# light.net
KiCad netlist of a schematic drawn in EAGLE
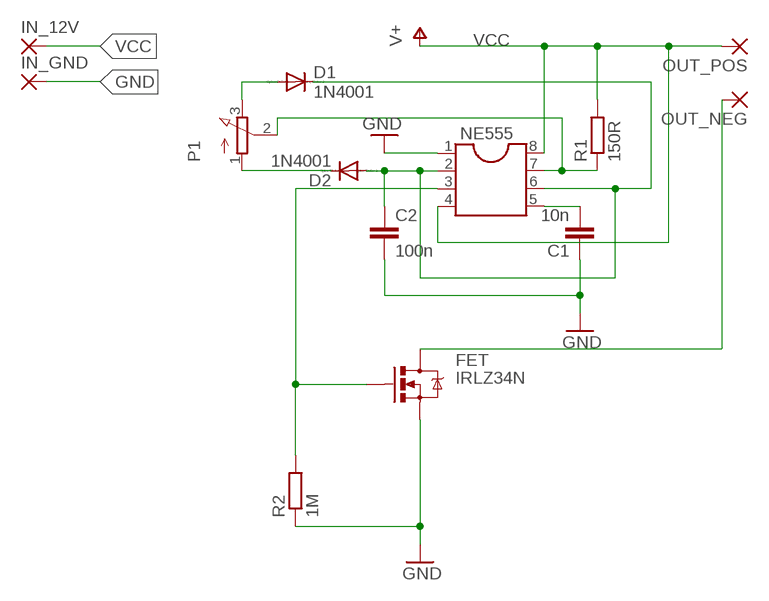
[diagram p0: schematic, sheet 1]

(export (version "E")
  (design (tool "Eeschema 10.0.6"))
  (components
    (comp (ref "C1")
      (value "10n")
      (footprint "eagle-import:C025-024X044")
      (libsource (lib "eagle-import") (part "C-EU025-024X044"))
    )
    (comp (ref "C2")
      (value "100n")
      (footprint "eagle-import:C025-024X044")
      (libsource (lib "eagle-import") (part "C-EU025-024X044"))
    )
    (comp (ref "D1")
      (value "1N4001")
      (footprint "eagle-import:DO41-10")
      (libsource (lib "eagle-import") (part "DIODE-DO41-10"))
    )
    (comp (ref "D2")
      (value "1N4001")
      (footprint "eagle-import:DO41-10")
      (libsource (lib "eagle-import") (part "DIODE-DO41-10"))
    )
    (comp (ref "FET")
      (value "IRLZ34N")
      (footprint "eagle-import:TO-220(2)")
      (fields (field (name "MF") "Infineon Technologies"))
      (libsource (lib "eagle-import") (part "IRLZ34N"))
    )
    (comp (ref "IN_12V")
      (value "3,81/1,3")
      (footprint "eagle-import:3,81_1,3")
      (libsource (lib "eagle-import") (part "3,81/1,3"))
    )
    (comp (ref "IN_GND")
      (value "3,81/1,3")
      (footprint "eagle-import:3,81_1,3")
      (libsource (lib "eagle-import") (part "3,81/1,3"))
    )
    (comp (ref "NE555")
      (value "DIL8")
      (footprint "eagle-import:DIL08")
      (libsource (lib "eagle-import") (part "DIL8"))
    )
    (comp (ref "OUT_NEG")
      (value "3,81/1,1")
      (footprint "eagle-import:3,81_1,1")
      (libsource (lib "eagle-import") (part "3,81/1,1"))
    )
    (comp (ref "OUT_POS")
      (value "3,81/1,1")
      (footprint "eagle-import:3,81_1,1")
      (libsource (lib "eagle-import") (part "3,81/1,1"))
    )
    (comp (ref "P1")
      (value "3RP/1610N")
      (footprint "eagle-import:3RP_1610N")
      (libsource (lib "eagle-import") (part "3RP/1610N"))
    )
    (comp (ref "R1")
      (value "150R")
      (footprint "eagle-import:0207_7")
      (libsource (lib "eagle-import") (part "R-EU_0207/7"))
    )
    (comp (ref "R2")
      (value "1M")
      (footprint "eagle-import:0207_7")
      (libsource (lib "eagle-import") (part "R-EU_0207/7"))
    )
  )
  (nets
    (net (code "1") (name "GND") (class "Default")
      (node (ref "C1") (pin "1") (pinfunction "1_1") (pintype "passive"))
      (node (ref "C2") (pin "2") (pinfunction "2_2") (pintype "passive"))
      (node (ref "FET") (pin "OUT") (pinfunction "S_OUT") (pintype "passive"))
      (node (ref "IN_GND") (pin "1") (pinfunction "P_1") (pintype "passive"))
      (node (ref "NE555") (pin "1") (pinfunction "1_1") (pintype "passive"))
      (node (ref "R2") (pin "1") (pinfunction "1_1") (pintype "passive"))
    )
    (net (code "2") (name "Net-(C1-Pad2)") (class "Default")
      (node (ref "C1") (pin "2") (pinfunction "2_2") (pintype "passive"))
      (node (ref "NE555") (pin "5") (pinfunction "5_5") (pintype "passive"))
    )
    (net (code "3") (name "Net-(C2-Pad1)") (class "Default")
      (node (ref "C2") (pin "1") (pinfunction "1_1") (pintype "passive"))
      (node (ref "D1") (pin "C") (pinfunction "C_C") (pintype "passive"))
      (node (ref "D2") (pin "A") (pinfunction "A_A") (pintype "passive"))
      (node (ref "NE555") (pin "2") (pinfunction "2_2") (pintype "passive"))
      (node (ref "NE555") (pin "6") (pinfunction "6_6") (pintype "passive"))
    )
    (net (code "4") (name "Net-(FET-D)") (class "Default")
      (node (ref "FET") (pin "GND") (pinfunction "D_GND") (pintype "passive"))
      (node (ref "OUT_NEG") (pin "1") (pinfunction "P_1") (pintype "passive"))
    )
    (net (code "5") (name "Net-(FET-G)") (class "Default")
      (node (ref "FET") (pin "IN") (pinfunction "G_IN") (pintype "passive"))
      (node (ref "NE555") (pin "3") (pinfunction "3_3") (pintype "passive"))
      (node (ref "R2") (pin "2") (pinfunction "2_2") (pintype "passive"))
    )
    (net (code "6") (name "Net-(P1-A)") (class "Default")
      (node (ref "D2") (pin "C") (pinfunction "C_C") (pintype "passive"))
      (node (ref "P1") (pin "1") (pinfunction "A_1") (pintype "passive"))
    )
    (net (code "7") (name "Net-(P1-E)") (class "Default")
      (node (ref "D1") (pin "A") (pinfunction "A_A") (pintype "passive"))
      (node (ref "P1") (pin "3") (pinfunction "E_3") (pintype "passive"))
    )
    (net (code "8") (name "Net-(P1-S)") (class "Default")
      (node (ref "NE555") (pin "7") (pinfunction "7_7") (pintype "passive"))
      (node (ref "P1") (pin "2") (pinfunction "S_2") (pintype "passive"))
      (node (ref "R1") (pin "1") (pinfunction "1_1") (pintype "passive"))
    )
    (net (code "9") (name "VCC") (class "Default")
      (node (ref "IN_12V") (pin "1") (pinfunction "P_1") (pintype "passive"))
      (node (ref "NE555") (pin "4") (pinfunction "4_4") (pintype "passive"))
      (node (ref "NE555") (pin "8") (pinfunction "8_8") (pintype "passive"))
      (node (ref "OUT_POS") (pin "1") (pinfunction "P_1") (pintype "passive"))
      (node (ref "R1") (pin "2") (pinfunction "2_2") (pintype "passive"))
    )
  )
)
